# OptoIso_L2H.net
KiCad netlist of a schematic drawn in Altium Designer
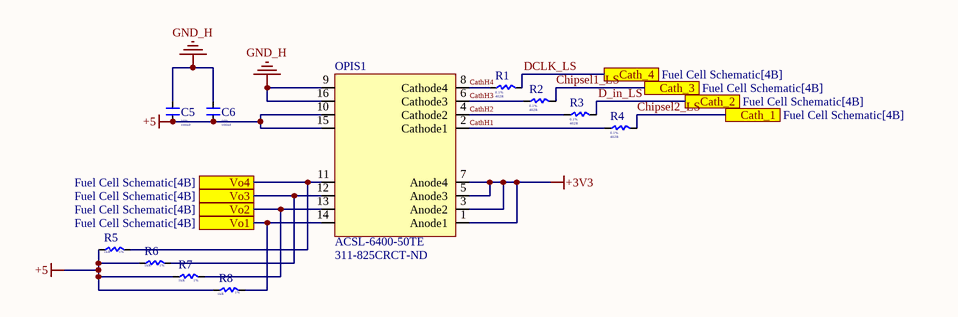
[diagram p0: OptoIso_L2H.SchDoc]

(export (version "E")
  (design (tool "Eeschema 10.0.6"))
  (components
    (comp (ref "C5")
      (value "~")
      (footprint "Capacitor_Kemet_0805")
      (description "Cap Ceramic 0.1uF 35V X7R 10% SMD 0805 125°C Paper T/R")
      (fields
        (field (name "MANUFACTURER") "KEMET")
        (field (name "MANUFACTURER PART NUMBER") "C0805C104K6RACTU")
        (field (name "TOLERANCE") "10%")
        (field (name "CAPACITANCE") "100nF")
      )
      (libsource (lib "Schlib1") (part "C0805C104K6RACTU"))
    )
    (comp (ref "C6")
      (value "~")
      (footprint "Capacitor_Kemet_0805")
      (description "Cap Ceramic 0.1uF 35V X7R 10% SMD 0805 125°C Paper T/R")
      (fields
        (field (name "MANUFACTURER") "KEMET")
        (field (name "MANUFACTURER PART NUMBER") "C0805C104K6RACTU")
        (field (name "TOLERANCE") "10%")
        (field (name "CAPACITANCE") "100nF")
      )
      (libsource (lib "Schlib1") (part "C0805C104K6RACTU"))
    )
    (comp (ref "OPIS1")
      (value "~")
      (footprint "Opto_Isolator_ACSL6400_50TE")
      (description "OPTOISO 2.5KV 4CH OPEN COLL 16SO")
      (fields
        (field (name "MANUFACTURER") "Broadcom Avago")
        (field (name "MANUFACTURER PART NUMBER") "ACSL-6400-50TE")
        (field (name "SUPPLIER PART NUMBER 2") "311-825CRCT-ND")
      )
      (libsource (lib "Schlib1") (part "ACSL-6400-50TE"))
    )
    (comp (ref "R1")
      (value "~")
      (footprint "LowR_Yageo")
      (description "Res Thin Film 0805 402 Ohm 0.1% 1/8W ±25ppm/°C Molded SMD Paper T/R")
      (fields
        (field (name "MANUFACTURER") "Yageo")
        (field (name "MANUFACTURER PART NUMBER") "RT0805BRD07402RL")
        (field (name "TOLERANCE") "0.1%")
        (field (name "RESISTANCE") "402R")
      )
      (libsource (lib "Schlib1") (part "RT0805BRD07402RL"))
    )
    (comp (ref "R2")
      (value "~")
      (footprint "LowR_Yageo")
      (description "Res Thin Film 0805 402 Ohm 0.1% 1/8W ±25ppm/°C Molded SMD Paper T/R")
      (fields
        (field (name "MANUFACTURER") "Yageo")
        (field (name "MANUFACTURER PART NUMBER") "RT0805BRD07402RL")
        (field (name "TOLERANCE") "0.1%")
        (field (name "RESISTANCE") "402R")
      )
      (libsource (lib "Schlib1") (part "RT0805BRD07402RL"))
    )
    (comp (ref "R3")
      (value "~")
      (footprint "LowR_Yageo")
      (description "Res Thin Film 0805 402 Ohm 0.1% 1/8W ±25ppm/°C Molded SMD Paper T/R")
      (fields
        (field (name "MANUFACTURER") "Yageo")
        (field (name "MANUFACTURER PART NUMBER") "RT0805BRD07402RL")
        (field (name "TOLERANCE") "0.1%")
        (field (name "RESISTANCE") "402R")
      )
      (libsource (lib "Schlib1") (part "RT0805BRD07402RL"))
    )
    (comp (ref "R4")
      (value "~")
      (footprint "LowR_Yageo")
      (description "Res Thin Film 0805 402 Ohm 0.1% 1/8W ±25ppm/°C Molded SMD Paper T/R")
      (fields
        (field (name "MANUFACTURER") "Yageo")
        (field (name "MANUFACTURER PART NUMBER") "RT0805BRD07402RL")
        (field (name "TOLERANCE") "0.1%")
        (field (name "RESISTANCE") "402R")
      )
      (libsource (lib "Schlib1") (part "RT0805BRD07402RL"))
    )
    (comp (ref "R5")
      (value "~")
      (footprint "Resistor_YAGEO_0805")
      (description "Res Thick Film 0805 1K Ohm 1% 0.125W(1/8W) ±100ppm/C Pad SMD T/R")
      (fields
        (field (name "MANUFACTURER") "Yageo")
        (field (name "MANUFACTURER PART NUMBER") "RC0805FR-071KP")
        (field (name "RESISTANCE") "1kR")
        (field (name "TOLERANCE") "1%")
      )
      (libsource (lib "Schlib1") (part "RC0805FR-071KP"))
    )
    (comp (ref "R6")
      (value "~")
      (footprint "Resistor_YAGEO_0805")
      (description "Res Thick Film 0805 1K Ohm 1% 0.125W(1/8W) ±100ppm/C Pad SMD T/R")
      (fields
        (field (name "MANUFACTURER") "Yageo")
        (field (name "MANUFACTURER PART NUMBER") "RC0805FR-071KP")
        (field (name "RESISTANCE") "1kR")
        (field (name "TOLERANCE") "1%")
      )
      (libsource (lib "Schlib1") (part "RC0805FR-071KP"))
    )
    (comp (ref "R7")
      (value "~")
      (footprint "Resistor_YAGEO_0805")
      (description "Res Thick Film 0805 1K Ohm 1% 0.125W(1/8W) ±100ppm/C Pad SMD T/R")
      (fields
        (field (name "MANUFACTURER") "Yageo")
        (field (name "MANUFACTURER PART NUMBER") "RC0805FR-071KP")
        (field (name "RESISTANCE") "1kR")
        (field (name "TOLERANCE") "1%")
      )
      (libsource (lib "Schlib1") (part "RC0805FR-071KP"))
    )
    (comp (ref "R8")
      (value "~")
      (footprint "Resistor_YAGEO_0805")
      (description "Res Thick Film 0805 1K Ohm 1% 0.125W(1/8W) ±100ppm/C Pad SMD T/R")
      (fields
        (field (name "MANUFACTURER") "Yageo")
        (field (name "MANUFACTURER PART NUMBER") "RC0805FR-071KP")
        (field (name "RESISTANCE") "1kR")
        (field (name "TOLERANCE") "1%")
      )
      (libsource (lib "Schlib1") (part "RC0805FR-071KP"))
    )
  )
  (nets
    (net (code "1") (name "+3V3") (class "Default")
      (node (ref "OPIS1") (pin "1") (pinfunction "Anode1_1") (pintype "passive"))
      (node (ref "OPIS1") (pin "3") (pinfunction "Anode2_3") (pintype "passive"))
      (node (ref "OPIS1") (pin "5") (pinfunction "Anode3_5") (pintype "passive"))
      (node (ref "OPIS1") (pin "7") (pinfunction "Anode4_7") (pintype "passive"))
    )
    (net (code "2") (name "+5") (class "Default")
      (node (ref "C5") (pin "2") (pinfunction "2_2") (pintype "passive"))
      (node (ref "C6") (pin "2") (pinfunction "2_2") (pintype "passive"))
      (node (ref "OPIS1") (pin "10") (pinfunction "VDD_10") (pintype "passive"))
      (node (ref "OPIS1") (pin "15") (pinfunction "VDD_15") (pintype "passive"))
      (node (ref "R5") (pin "1") (pinfunction "1_1") (pintype "passive"))
      (node (ref "R6") (pin "1") (pinfunction "1_1") (pintype "passive"))
      (node (ref "R7") (pin "1") (pinfunction "1_1") (pintype "passive"))
      (node (ref "R8") (pin "1") (pinfunction "1_1") (pintype "passive"))
    )
    (net (code "3") (name "/CathH1") (class "Default")
      (node (ref "OPIS1") (pin "2") (pinfunction "Cathode1_2") (pintype "passive"))
      (node (ref "R4") (pin "1") (pinfunction "1_1") (pintype "passive"))
    )
    (net (code "4") (name "/CathH2") (class "Default")
      (node (ref "OPIS1") (pin "4") (pinfunction "Cathode2_4") (pintype "passive"))
      (node (ref "R3") (pin "1") (pinfunction "1_1") (pintype "passive"))
    )
    (net (code "5") (name "/CathH3") (class "Default")
      (node (ref "OPIS1") (pin "6") (pinfunction "Cathode3_6") (pintype "passive"))
      (node (ref "R2") (pin "1") (pinfunction "1_1") (pintype "passive"))
    )
    (net (code "6") (name "/CathH4") (class "Default")
      (node (ref "OPIS1") (pin "8") (pinfunction "Cathode4_8") (pintype "passive"))
      (node (ref "R1") (pin "1") (pinfunction "1_1") (pintype "passive"))
    )
    (net (code "7") (name "/Chipsel1_LS") (class "Default")
      (node (ref "R2") (pin "2") (pinfunction "2_2") (pintype "passive"))
    )
    (net (code "8") (name "/Chipsel2_LS") (class "Default")
      (node (ref "R4") (pin "2") (pinfunction "2_2") (pintype "passive"))
    )
    (net (code "9") (name "/DCLK_LS") (class "Default")
      (node (ref "R1") (pin "2") (pinfunction "2_2") (pintype "passive"))
    )
    (net (code "10") (name "/D_in_LS") (class "Default")
      (node (ref "R3") (pin "2") (pinfunction "2_2") (pintype "passive"))
    )
    (net (code "11") (name "/Vo1") (class "Default")
      (node (ref "OPIS1") (pin "14") (pinfunction "Vo1_14") (pintype "passive"))
      (node (ref "R8") (pin "2") (pinfunction "2_2") (pintype "passive"))
    )
    (net (code "12") (name "/Vo2") (class "Default")
      (node (ref "OPIS1") (pin "13") (pinfunction "Vo2_13") (pintype "passive"))
      (node (ref "R7") (pin "2") (pinfunction "2_2") (pintype "passive"))
    )
    (net (code "13") (name "/Vo3") (class "Default")
      (node (ref "OPIS1") (pin "12") (pinfunction "Vo3_12") (pintype "passive"))
      (node (ref "R6") (pin "2") (pinfunction "2_2") (pintype "passive"))
    )
    (net (code "14") (name "/Vo4") (class "Default")
      (node (ref "OPIS1") (pin "11") (pinfunction "Vo4_11") (pintype "passive"))
      (node (ref "R5") (pin "2") (pinfunction "2_2") (pintype "passive"))
    )
    (net (code "15") (name "GND_H") (class "Default")
      (node (ref "C5") (pin "1") (pinfunction "1_1") (pintype "passive"))
      (node (ref "C6") (pin "1") (pinfunction "1_1") (pintype "passive"))
      (node (ref "OPIS1") (pin "16") (pinfunction "Ground_16") (pintype "passive"))
      (node (ref "OPIS1") (pin "9") (pinfunction "Ground_9") (pintype "passive"))
    )
  )
)
